# plytka.net
KiCad netlist of a schematic drawn in EAGLE
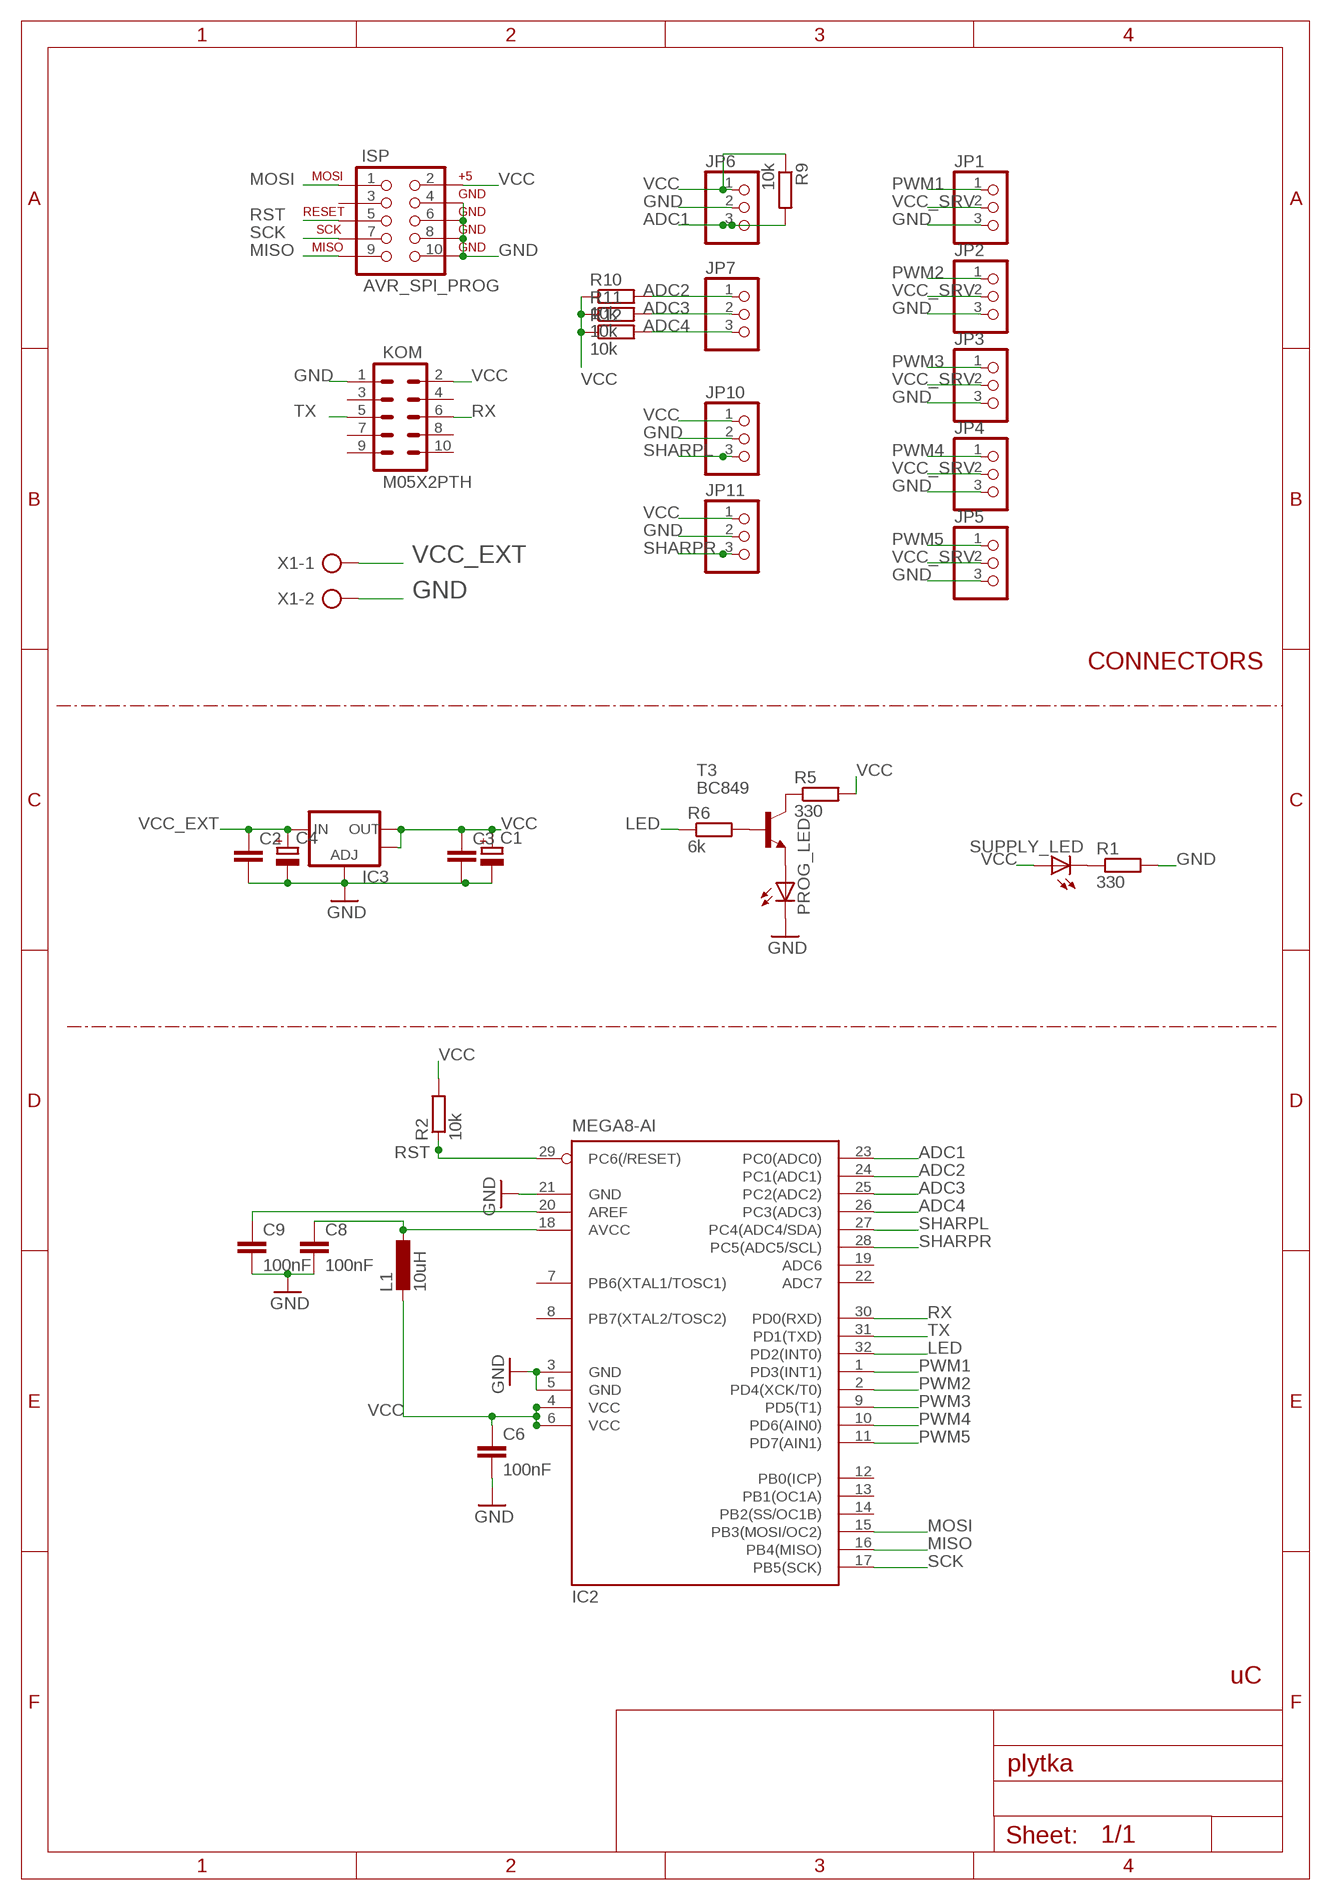
[diagram p0: schematic, sheet 1]

(export (version "E")
  (design (tool "Eeschema 10.0.6"))
  (components
    (comp (ref "C1")
      (value "CPOL-EUE5-10.5")
      (footprint "eagle-import:E5-10,5")
      (libsource (lib "eagle-import") (part "CPOL-EUE5-10.5"))
    )
    (comp (ref "C2")
      (value "C-EUC0805")
      (footprint "eagle-import:C0805")
      (libsource (lib "eagle-import") (part "C-EUC0805"))
    )
    (comp (ref "C3")
      (value "C-EUC0805")
      (footprint "eagle-import:C0805")
      (libsource (lib "eagle-import") (part "C-EUC0805"))
    )
    (comp (ref "C4")
      (value "CPOL-EUE5-10.5")
      (footprint "eagle-import:E5-10,5")
      (libsource (lib "eagle-import") (part "CPOL-EUE5-10.5"))
    )
    (comp (ref "C6")
      (value "100nF")
      (footprint "eagle-import:C0805")
      (libsource (lib "eagle-import") (part "C-EUC0805"))
    )
    (comp (ref "C8")
      (value "100nF")
      (footprint "eagle-import:C0805")
      (libsource (lib "eagle-import") (part "C-EUC0805"))
    )
    (comp (ref "C9")
      (value "100nF")
      (footprint "eagle-import:C0805")
      (libsource (lib "eagle-import") (part "C-EUC0805"))
    )
    (comp (ref "IC2")
      (value "MEGA8-AI")
      (footprint "eagle-import:TQFP32-08")
      (libsource (lib "eagle-import") (part "MEGA8-AI"))
    )
    (comp (ref "IC3")
      (value "V_REG_LM1117SOT223")
      (footprint "eagle-import:SOT223")
      (libsource (lib "eagle-import") (part "V_REG_LM1117SOT223"))
    )
    (comp (ref "ISP")
      (value "AVR_SPI_PROG")
      (footprint "eagle-import:AVR_ICSP")
      (libsource (lib "eagle-import") (part "AVR_SPI_PROG"))
    )
    (comp (ref "JP1")
      (value "PINHD-1X3")
      (footprint "eagle-import:1X03")
      (libsource (lib "eagle-import") (part "PINHD-1X3"))
    )
    (comp (ref "JP2")
      (value "PINHD-1X3")
      (footprint "eagle-import:1X03")
      (libsource (lib "eagle-import") (part "PINHD-1X3"))
    )
    (comp (ref "JP3")
      (value "PINHD-1X3")
      (footprint "eagle-import:1X03")
      (libsource (lib "eagle-import") (part "PINHD-1X3"))
    )
    (comp (ref "JP4")
      (value "PINHD-1X3")
      (footprint "eagle-import:1X03")
      (libsource (lib "eagle-import") (part "PINHD-1X3"))
    )
    (comp (ref "JP5")
      (value "PINHD-1X3")
      (footprint "eagle-import:1X03")
      (libsource (lib "eagle-import") (part "PINHD-1X3"))
    )
    (comp (ref "JP6")
      (value "PINHD-1X3")
      (footprint "eagle-import:1X03")
      (libsource (lib "eagle-import") (part "PINHD-1X3"))
    )
    (comp (ref "JP7")
      (value "PINHD-1X3")
      (footprint "eagle-import:1X03")
      (libsource (lib "eagle-import") (part "PINHD-1X3"))
    )
    (comp (ref "JP10")
      (value "PINHD-1X3")
      (footprint "eagle-import:1X03")
      (libsource (lib "eagle-import") (part "PINHD-1X3"))
    )
    (comp (ref "JP11")
      (value "PINHD-1X3")
      (footprint "eagle-import:1X03")
      (libsource (lib "eagle-import") (part "PINHD-1X3"))
    )
    (comp (ref "KOM")
      (value "M05X2PTH")
      (footprint "eagle-import:AVR_ICSP")
      (libsource (lib "eagle-import") (part "M05X2PTH"))
    )
    (comp (ref "L1")
      (value "10uH")
      (footprint "eagle-import:L2012C")
      (libsource (lib "eagle-import") (part "L-EUL2012C"))
    )
    (comp (ref "PROG_LED")
      (value "LEDCHIPLED_0805")
      (footprint "eagle-import:CHIPLED_0805")
      (libsource (lib "eagle-import") (part "LEDCHIPLED_0805"))
    )
    (comp (ref "R1")
      (value "330")
      (footprint "eagle-import:R0805")
      (libsource (lib "eagle-import") (part "R-EU_R0805"))
    )
    (comp (ref "R2")
      (value "10k")
      (footprint "eagle-import:M0805")
      (libsource (lib "eagle-import") (part "R-EU_M0805"))
    )
    (comp (ref "R5")
      (value "330")
      (footprint "eagle-import:R0805")
      (libsource (lib "eagle-import") (part "R-EU_R0805"))
    )
    (comp (ref "R6")
      (value "6k")
      (footprint "eagle-import:R0805")
      (libsource (lib "eagle-import") (part "R-EU_R0805"))
    )
    (comp (ref "R9")
      (value "10k")
      (footprint "eagle-import:M0805")
      (libsource (lib "eagle-import") (part "R-EU_M0805"))
    )
    (comp (ref "R10")
      (value "10k")
      (footprint "eagle-import:M0805")
      (libsource (lib "eagle-import") (part "R-EU_M0805"))
    )
    (comp (ref "R11")
      (value "10k")
      (footprint "eagle-import:M0805")
      (libsource (lib "eagle-import") (part "R-EU_M0805"))
    )
    (comp (ref "R12")
      (value "10k")
      (footprint "eagle-import:M0805")
      (libsource (lib "eagle-import") (part "R-EU_M0805"))
    )
    (comp (ref "SUPPLY_LED")
      (value "LEDCHIPLED_0805")
      (footprint "eagle-import:CHIPLED_0805")
      (libsource (lib "eagle-import") (part "LEDCHIPLED_0805"))
    )
    (comp (ref "T3")
      (value "BC849")
      (footprint "eagle-import:SOT23")
      (libsource (lib "eagle-import") (part "BC849"))
    )
    (comp (ref "X1")
      (value "AK300/2")
      (footprint "eagle-import:AK300_2")
      (libsource (lib "eagle-import") (part "AK300/2"))
    )
  )
  (nets
    (net (code "1") (name "/ADC1") (class "Default")
      (node (ref "IC2") (pin "23") (pinfunction "PC0(ADC0)_23") (pintype "bidirectional"))
      (node (ref "JP6") (pin "3") (pinfunction "3_3") (pintype "passive"))
      (node (ref "R9") (pin "2") (pinfunction "2_2") (pintype "passive"))
    )
    (net (code "2") (name "/ADC2") (class "Default")
      (node (ref "IC2") (pin "24") (pinfunction "PC1(ADC1)_24") (pintype "bidirectional"))
      (node (ref "JP7") (pin "1") (pinfunction "1_1") (pintype "passive"))
      (node (ref "R10") (pin "2") (pinfunction "2_2") (pintype "passive"))
    )
    (net (code "3") (name "/ADC3") (class "Default")
      (node (ref "IC2") (pin "25") (pinfunction "PC2(ADC2)_25") (pintype "bidirectional"))
      (node (ref "JP7") (pin "2") (pinfunction "2_2") (pintype "passive"))
      (node (ref "R11") (pin "2") (pinfunction "2_2") (pintype "passive"))
    )
    (net (code "4") (name "/ADC4") (class "Default")
      (node (ref "IC2") (pin "26") (pinfunction "PC3(ADC3)_26") (pintype "bidirectional"))
      (node (ref "JP7") (pin "3") (pinfunction "3_3") (pintype "passive"))
      (node (ref "R12") (pin "2") (pinfunction "2_2") (pintype "passive"))
    )
    (net (code "5") (name "/LED") (class "Default")
      (node (ref "IC2") (pin "32") (pinfunction "PD2(INT0)_32") (pintype "bidirectional"))
      (node (ref "R6") (pin "1") (pinfunction "1_1") (pintype "passive"))
    )
    (net (code "6") (name "/MISO") (class "Default")
      (node (ref "IC2") (pin "16") (pinfunction "PB4(MISO)_16") (pintype "bidirectional"))
      (node (ref "ISP") (pin "9") (pinfunction "9_9") (pintype "passive"))
    )
    (net (code "7") (name "/MOSI") (class "Default")
      (node (ref "IC2") (pin "15") (pinfunction "PB3(MOSI/OC2)_15") (pintype "bidirectional"))
      (node (ref "ISP") (pin "1") (pinfunction "1_1") (pintype "passive"))
    )
    (net (code "8") (name "/PWM1") (class "Default")
      (node (ref "IC2") (pin "1") (pinfunction "PD3(INT1)_1") (pintype "bidirectional"))
      (node (ref "JP1") (pin "1") (pinfunction "1_1") (pintype "passive"))
    )
    (net (code "9") (name "/PWM2") (class "Default")
      (node (ref "IC2") (pin "2") (pinfunction "PD4(XCK/T0)_2") (pintype "bidirectional"))
      (node (ref "JP2") (pin "1") (pinfunction "1_1") (pintype "passive"))
    )
    (net (code "10") (name "/PWM3") (class "Default")
      (node (ref "IC2") (pin "9") (pinfunction "PD5(T1)_9") (pintype "bidirectional"))
      (node (ref "JP3") (pin "1") (pinfunction "1_1") (pintype "passive"))
    )
    (net (code "11") (name "/PWM4") (class "Default")
      (node (ref "IC2") (pin "10") (pinfunction "PD6(AIN0)_10") (pintype "bidirectional"))
      (node (ref "JP4") (pin "1") (pinfunction "1_1") (pintype "passive"))
    )
    (net (code "12") (name "/PWM5") (class "Default")
      (node (ref "IC2") (pin "11") (pinfunction "PD7(AIN1)_11") (pintype "bidirectional"))
      (node (ref "JP5") (pin "1") (pinfunction "1_1") (pintype "passive"))
    )
    (net (code "13") (name "/RST") (class "Default")
      (node (ref "IC2") (pin "29") (pinfunction "PC6(/RESET)_29") (pintype "bidirectional"))
      (node (ref "ISP") (pin "5") (pinfunction "5_5") (pintype "passive"))
      (node (ref "R2") (pin "1") (pinfunction "1_1") (pintype "passive"))
    )
    (net (code "14") (name "/RX") (class "Default")
      (node (ref "IC2") (pin "30") (pinfunction "PD0(RXD)_30") (pintype "bidirectional"))
      (node (ref "KOM") (pin "6") (pinfunction "6_6") (pintype "passive"))
    )
    (net (code "15") (name "/SCK") (class "Default")
      (node (ref "IC2") (pin "17") (pinfunction "PB5(SCK)_17") (pintype "bidirectional"))
      (node (ref "ISP") (pin "7") (pinfunction "7_7") (pintype "passive"))
    )
    (net (code "16") (name "/SHARPL") (class "Default")
      (node (ref "IC2") (pin "27") (pinfunction "PC4(ADC4/SDA)_27") (pintype "bidirectional"))
      (node (ref "JP10") (pin "3") (pinfunction "3_3") (pintype "passive"))
    )
    (net (code "17") (name "/SHARPR") (class "Default")
      (node (ref "IC2") (pin "28") (pinfunction "PC5(ADC5/SCL)_28") (pintype "bidirectional"))
      (node (ref "JP11") (pin "3") (pinfunction "3_3") (pintype "passive"))
    )
    (net (code "18") (name "/TX") (class "Default")
      (node (ref "IC2") (pin "31") (pinfunction "PD1(TXD)_31") (pintype "bidirectional"))
      (node (ref "KOM") (pin "5") (pinfunction "5_5") (pintype "passive"))
    )
    (net (code "19") (name "/VCC") (class "Default")
      (node (ref "C1") (pin "+") (pinfunction "+_+") (pintype "passive"))
      (node (ref "C3") (pin "1") (pinfunction "1_1") (pintype "passive"))
      (node (ref "C6") (pin "1") (pinfunction "1_1") (pintype "passive"))
      (node (ref "IC2") (pin "4") (pinfunction "VCC_4") (pintype "power_in"))
      (node (ref "IC2") (pin "6") (pinfunction "VCC_6") (pintype "power_in"))
      (node (ref "IC3") (pin "2") (pinfunction "OUT_2") (pintype "output"))
      (node (ref "IC3") (pin "4") (pinfunction "OUT_4") (pintype "output"))
      (node (ref "ISP") (pin "2") (pinfunction "2_2") (pintype "passive"))
      (node (ref "JP10") (pin "1") (pinfunction "1_1") (pintype "passive"))
      (node (ref "JP11") (pin "1") (pinfunction "1_1") (pintype "passive"))
      (node (ref "JP6") (pin "1") (pinfunction "1_1") (pintype "passive"))
      (node (ref "KOM") (pin "2") (pinfunction "2_2") (pintype "passive"))
      (node (ref "L1") (pin "2") (pinfunction "2_2") (pintype "passive"))
      (node (ref "R10") (pin "1") (pinfunction "1_1") (pintype "passive"))
      (node (ref "R11") (pin "1") (pinfunction "1_1") (pintype "passive"))
      (node (ref "R12") (pin "1") (pinfunction "1_1") (pintype "passive"))
      (node (ref "R2") (pin "2") (pinfunction "2_2") (pintype "passive"))
      (node (ref "R5") (pin "2") (pinfunction "2_2") (pintype "passive"))
      (node (ref "R9") (pin "1") (pinfunction "1_1") (pintype "passive"))
      (node (ref "SUPPLY_LED") (pin "A") (pinfunction "A_A") (pintype "passive"))
    )
    (net (code "20") (name "/VCC_EXT") (class "Default")
      (node (ref "C2") (pin "1") (pinfunction "1_1") (pintype "passive"))
      (node (ref "C4") (pin "+") (pinfunction "+_+") (pintype "passive"))
      (node (ref "IC3") (pin "3") (pinfunction "IN_3") (pintype "input"))
      (node (ref "X1") (pin "1") (pinfunction "KL_1") (pintype "passive"))
    )
    (net (code "21") (name "/VCC_SRV") (class "Default")
      (node (ref "JP1") (pin "2") (pinfunction "2_2") (pintype "passive"))
      (node (ref "JP2") (pin "2") (pinfunction "2_2") (pintype "passive"))
      (node (ref "JP3") (pin "2") (pinfunction "2_2") (pintype "passive"))
      (node (ref "JP4") (pin "2") (pinfunction "2_2") (pintype "passive"))
      (node (ref "JP5") (pin "2") (pinfunction "2_2") (pintype "passive"))
    )
    (net (code "22") (name "GND") (class "Default")
      (node (ref "C1") (pin "-") (pinfunction "-_-") (pintype "passive"))
      (node (ref "C2") (pin "2") (pinfunction "2_2") (pintype "passive"))
      (node (ref "C3") (pin "2") (pinfunction "2_2") (pintype "passive"))
      (node (ref "C4") (pin "-") (pinfunction "-_-") (pintype "passive"))
      (node (ref "C6") (pin "2") (pinfunction "2_2") (pintype "passive"))
      (node (ref "C8") (pin "2") (pinfunction "2_2") (pintype "passive"))
      (node (ref "C9") (pin "2") (pinfunction "2_2") (pintype "passive"))
      (node (ref "IC2") (pin "21") (pinfunction "GND_21") (pintype "power_in"))
      (node (ref "IC2") (pin "3") (pinfunction "GND_3") (pintype "power_in"))
      (node (ref "IC2") (pin "5") (pinfunction "GND_5") (pintype "power_in"))
      (node (ref "IC3") (pin "1") (pinfunction "ADJ_1") (pintype "input"))
      (node (ref "ISP") (pin "10") (pinfunction "10_10") (pintype "passive"))
      (node (ref "ISP") (pin "4") (pinfunction "4_4") (pintype "passive"))
      (node (ref "ISP") (pin "6") (pinfunction "6_6") (pintype "passive"))
      (node (ref "ISP") (pin "8") (pinfunction "8_8") (pintype "passive"))
      (node (ref "JP1") (pin "3") (pinfunction "3_3") (pintype "passive"))
      (node (ref "JP10") (pin "2") (pinfunction "2_2") (pintype "passive"))
      (node (ref "JP11") (pin "2") (pinfunction "2_2") (pintype "passive"))
      (node (ref "JP2") (pin "3") (pinfunction "3_3") (pintype "passive"))
      (node (ref "JP3") (pin "3") (pinfunction "3_3") (pintype "passive"))
      (node (ref "JP4") (pin "3") (pinfunction "3_3") (pintype "passive"))
      (node (ref "JP5") (pin "3") (pinfunction "3_3") (pintype "passive"))
      (node (ref "JP6") (pin "2") (pinfunction "2_2") (pintype "passive"))
      (node (ref "KOM") (pin "1") (pinfunction "1_1") (pintype "passive"))
      (node (ref "PROG_LED") (pin "C") (pinfunction "C_C") (pintype "passive"))
      (node (ref "R1") (pin "2") (pinfunction "2_2") (pintype "passive"))
      (node (ref "X1") (pin "2") (pinfunction "KL_2") (pintype "passive"))
    )
    (net (code "23") (name "Net-(IC2-AREF)") (class "Default")
      (node (ref "C9") (pin "1") (pinfunction "1_1") (pintype "passive"))
      (node (ref "IC2") (pin "20") (pinfunction "AREF_20") (pintype "passive"))
    )
    (net (code "24") (name "Net-(IC2-AVCC)") (class "Default")
      (node (ref "C8") (pin "1") (pinfunction "1_1") (pintype "passive"))
      (node (ref "IC2") (pin "18") (pinfunction "AVCC_18") (pintype "power_in"))
      (node (ref "L1") (pin "1") (pinfunction "1_1") (pintype "passive"))
    )
    (net (code "25") (name "Net-(R1-Pad1)") (class "Default")
      (node (ref "R1") (pin "1") (pinfunction "1_1") (pintype "passive"))
      (node (ref "SUPPLY_LED") (pin "C") (pinfunction "C_C") (pintype "passive"))
    )
    (net (code "26") (name "Net-(T3-B)") (class "Default")
      (node (ref "R6") (pin "2") (pinfunction "2_2") (pintype "passive"))
      (node (ref "T3") (pin "1") (pinfunction "B_1") (pintype "passive"))
    )
    (net (code "27") (name "Net-(T3-C)") (class "Default")
      (node (ref "R5") (pin "1") (pinfunction "1_1") (pintype "passive"))
      (node (ref "T3") (pin "3") (pinfunction "C_3") (pintype "passive"))
    )
    (net (code "28") (name "Net-(T3-E)") (class "Default")
      (node (ref "PROG_LED") (pin "A") (pinfunction "A_A") (pintype "passive"))
      (node (ref "T3") (pin "2") (pinfunction "E_2") (pintype "passive"))
    )
    (net (code "29") (name "unconnected-(IC2-ADC6-Pad19)") (class "Default")
      (node (ref "IC2") (pin "19") (pinfunction "ADC6_19") (pintype "bidirectional"))
    )
    (net (code "30") (name "unconnected-(IC2-ADC7-Pad22)") (class "Default")
      (node (ref "IC2") (pin "22") (pinfunction "ADC7_22") (pintype "bidirectional"))
    )
    (net (code "31") (name "unconnected-(IC2-PB0(ICP)-Pad12)") (class "Default")
      (node (ref "IC2") (pin "12") (pinfunction "PB0(ICP)_12") (pintype "bidirectional"))
    )
    (net (code "32") (name "unconnected-(IC2-PB1(OC1A)-Pad13)") (class "Default")
      (node (ref "IC2") (pin "13") (pinfunction "PB1(OC1A)_13") (pintype "bidirectional"))
    )
    (net (code "33") (name "unconnected-(IC2-PB2(SS{slash}OC1B)-Pad14)") (class "Default")
      (node (ref "IC2") (pin "14") (pinfunction "PB2(SS/OC1B)_14") (pintype "bidirectional"))
    )
    (net (code "34") (name "unconnected-(IC2-PB6(XTAL1{slash}TOSC1)-Pad7)") (class "Default")
      (node (ref "IC2") (pin "7") (pinfunction "PB6(XTAL1/TOSC1)_7") (pintype "bidirectional"))
    )
    (net (code "35") (name "unconnected-(IC2-PB7(XTAL2{slash}TOSC2)-Pad8)") (class "Default")
      (node (ref "IC2") (pin "8") (pinfunction "PB7(XTAL2/TOSC2)_8") (pintype "bidirectional"))
    )
    (net (code "36") (name "unconnected-(ISP-Pad3)") (class "Default")
      (node (ref "ISP") (pin "3") (pinfunction "3_3") (pintype "passive"))
    )
    (net (code "37") (name "unconnected-(KOM-Pad3)") (class "Default")
      (node (ref "KOM") (pin "3") (pinfunction "3_3") (pintype "passive"))
    )
    (net (code "38") (name "unconnected-(KOM-Pad4)") (class "Default")
      (node (ref "KOM") (pin "4") (pinfunction "4_4") (pintype "passive"))
    )
    (net (code "39") (name "unconnected-(KOM-Pad7)") (class "Default")
      (node (ref "KOM") (pin "7") (pinfunction "7_7") (pintype "passive"))
    )
    (net (code "40") (name "unconnected-(KOM-Pad8)") (class "Default")
      (node (ref "KOM") (pin "8") (pinfunction "8_8") (pintype "passive"))
    )
    (net (code "41") (name "unconnected-(KOM-Pad9)") (class "Default")
      (node (ref "KOM") (pin "9") (pinfunction "9_9") (pintype "passive"))
    )
    (net (code "42") (name "unconnected-(KOM-Pad10)") (class "Default")
      (node (ref "KOM") (pin "10") (pinfunction "10_10") (pintype "passive"))
    )
  )
)
